# minimega.net
KiCad netlist of a schematic drawn in EAGLE
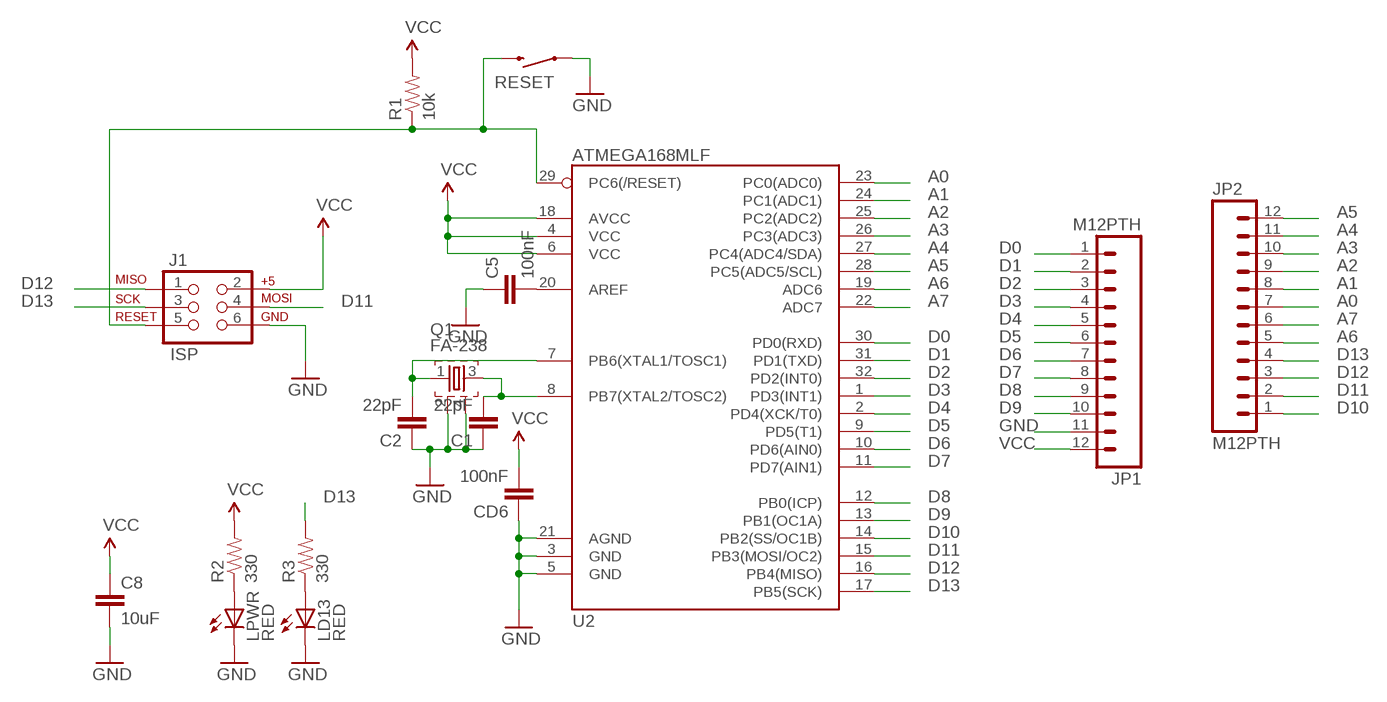
[diagram p0: schematic, sheet 1]

(export (version "E")
  (design (tool "Eeschema 10.0.6"))
  (components
    (comp (ref "C1")
      (value "22pF")
      (footprint "eagle-import:0402-CAP")
      (libsource (lib "eagle-import") (part "10NF-CER"))
    )
    (comp (ref "C2")
      (value "22pF")
      (footprint "eagle-import:0402-CAP")
      (libsource (lib "eagle-import") (part "10NF-CER"))
    )
    (comp (ref "C5")
      (value "100nF")
      (footprint "eagle-import:0402-CAP")
      (libsource (lib "eagle-import") (part "10NF-CER"))
    )
    (comp (ref "C8")
      (value "10uF")
      (footprint "eagle-import:0805")
      (libsource (lib "eagle-import") (part "CAP0805"))
    )
    (comp (ref "CD6")
      (value "100nF")
      (footprint "eagle-import:0402-CAP")
      (libsource (lib "eagle-import") (part "10NF-CER"))
    )
    (comp (ref "J1")
      (value "ISP")
      (footprint "eagle-import:2X3")
      (libsource (lib "eagle-import") (part "AVR_SPI_PRG_6PTH"))
    )
    (comp (ref "JP1")
      (value "M12PTH")
      (footprint "eagle-import:1X12")
      (libsource (lib "eagle-import") (part "M12PTH"))
    )
    (comp (ref "JP2")
      (value "M12PTH")
      (footprint "eagle-import:1X12")
      (libsource (lib "eagle-import") (part "M12PTH"))
    )
    (comp (ref "LD13")
      (value "RED")
      (footprint "eagle-import:LED-0603")
      (libsource (lib "eagle-import") (part "LED-RED0603"))
    )
    (comp (ref "LPWR")
      (value "RED")
      (footprint "eagle-import:LED-0603")
      (libsource (lib "eagle-import") (part "LED-RED0603"))
    )
    (comp (ref "Q1")
      (value "FA-238")
      (footprint "eagle-import:FA-238")
      (libsource (lib "eagle-import") (part "FA-238"))
    )
    (comp (ref "R1")
      (value "10k")
      (footprint "eagle-import:0603-RES")
      (libsource (lib "eagle-import") (part "RESISTOR0603"))
    )
    (comp (ref "R2")
      (value "330")
      (footprint "eagle-import:0603-RES")
      (libsource (lib "eagle-import") (part "RESISTOR0603"))
    )
    (comp (ref "R3")
      (value "330")
      (footprint "eagle-import:0603-RES")
      (libsource (lib "eagle-import") (part "RESISTOR0603"))
    )
    (comp (ref "RESET")
      (value "SWITCH-MOMENTARY-2PTH")
      (footprint "eagle-import:TACTILE-PTH")
      (libsource (lib "eagle-import") (part "SWITCH-MOMENTARY-2PTH"))
    )
    (comp (ref "U2")
      (value "ATMEGA168MLF")
      (footprint "eagle-import:MLF32")
      (libsource (lib "eagle-import") (part "ATMEGA168MLF"))
    )
  )
  (nets
    (net (code "1") (name "/A0") (class "Default")
      (node (ref "JP2") (pin "7") (pinfunction "7_7") (pintype "passive"))
      (node (ref "U2") (pin "23") (pinfunction "PC0(ADC0)_23") (pintype "bidirectional"))
    )
    (net (code "2") (name "/A1") (class "Default")
      (node (ref "JP2") (pin "8") (pinfunction "8_8") (pintype "passive"))
      (node (ref "U2") (pin "24") (pinfunction "PC1(ADC1)_24") (pintype "bidirectional"))
    )
    (net (code "3") (name "/A2") (class "Default")
      (node (ref "JP2") (pin "9") (pinfunction "9_9") (pintype "passive"))
      (node (ref "U2") (pin "25") (pinfunction "PC2(ADC2)_25") (pintype "bidirectional"))
    )
    (net (code "4") (name "/A3") (class "Default")
      (node (ref "JP2") (pin "10") (pinfunction "10_10") (pintype "passive"))
      (node (ref "U2") (pin "26") (pinfunction "PC3(ADC3)_26") (pintype "bidirectional"))
    )
    (net (code "5") (name "/A4") (class "Default")
      (node (ref "JP2") (pin "11") (pinfunction "11_11") (pintype "passive"))
      (node (ref "U2") (pin "27") (pinfunction "PC4(ADC4/SDA)_27") (pintype "bidirectional"))
    )
    (net (code "6") (name "/A5") (class "Default")
      (node (ref "JP2") (pin "12") (pinfunction "12_12") (pintype "passive"))
      (node (ref "U2") (pin "28") (pinfunction "PC5(ADC5/SCL)_28") (pintype "bidirectional"))
    )
    (net (code "7") (name "/A6") (class "Default")
      (node (ref "JP2") (pin "5") (pinfunction "5_5") (pintype "passive"))
      (node (ref "U2") (pin "19") (pinfunction "ADC6_19") (pintype "bidirectional"))
    )
    (net (code "8") (name "/A7") (class "Default")
      (node (ref "JP2") (pin "6") (pinfunction "6_6") (pintype "passive"))
      (node (ref "U2") (pin "22") (pinfunction "ADC7_22") (pintype "bidirectional"))
    )
    (net (code "9") (name "/D0") (class "Default")
      (node (ref "JP1") (pin "1") (pinfunction "1_1") (pintype "passive"))
      (node (ref "U2") (pin "30") (pinfunction "PD0(RXD)_30") (pintype "bidirectional"))
    )
    (net (code "10") (name "/D1") (class "Default")
      (node (ref "JP1") (pin "2") (pinfunction "2_2") (pintype "passive"))
      (node (ref "U2") (pin "31") (pinfunction "PD1(TXD)_31") (pintype "bidirectional"))
    )
    (net (code "11") (name "/D2") (class "Default")
      (node (ref "JP1") (pin "3") (pinfunction "3_3") (pintype "passive"))
      (node (ref "U2") (pin "32") (pinfunction "PD2(INT0)_32") (pintype "bidirectional"))
    )
    (net (code "12") (name "/D3") (class "Default")
      (node (ref "JP1") (pin "4") (pinfunction "4_4") (pintype "passive"))
      (node (ref "U2") (pin "1") (pinfunction "PD3(INT1)_1") (pintype "bidirectional"))
    )
    (net (code "13") (name "/D4") (class "Default")
      (node (ref "JP1") (pin "5") (pinfunction "5_5") (pintype "passive"))
      (node (ref "U2") (pin "2") (pinfunction "PD4(XCK/T0)_2") (pintype "bidirectional"))
    )
    (net (code "14") (name "/D5") (class "Default")
      (node (ref "JP1") (pin "6") (pinfunction "6_6") (pintype "passive"))
      (node (ref "U2") (pin "9") (pinfunction "PD5(T1)_9") (pintype "bidirectional"))
    )
    (net (code "15") (name "/D6") (class "Default")
      (node (ref "JP1") (pin "7") (pinfunction "7_7") (pintype "passive"))
      (node (ref "U2") (pin "10") (pinfunction "PD6(AIN0)_10") (pintype "bidirectional"))
    )
    (net (code "16") (name "/D7") (class "Default")
      (node (ref "JP1") (pin "8") (pinfunction "8_8") (pintype "passive"))
      (node (ref "U2") (pin "11") (pinfunction "PD7(AIN1)_11") (pintype "bidirectional"))
    )
    (net (code "17") (name "/D8") (class "Default")
      (node (ref "JP1") (pin "9") (pinfunction "9_9") (pintype "passive"))
      (node (ref "U2") (pin "12") (pinfunction "PB0(ICP)_12") (pintype "bidirectional"))
    )
    (net (code "18") (name "/D9") (class "Default")
      (node (ref "JP1") (pin "10") (pinfunction "10_10") (pintype "passive"))
      (node (ref "U2") (pin "13") (pinfunction "PB1(OC1A)_13") (pintype "bidirectional"))
    )
    (net (code "19") (name "/D10") (class "Default")
      (node (ref "JP2") (pin "1") (pinfunction "1_1") (pintype "passive"))
      (node (ref "U2") (pin "14") (pinfunction "PB2(SS/OC1B)_14") (pintype "bidirectional"))
    )
    (net (code "20") (name "/D11") (class "Default")
      (node (ref "J1") (pin "4") (pinfunction "4_4") (pintype "passive"))
      (node (ref "JP2") (pin "2") (pinfunction "2_2") (pintype "passive"))
      (node (ref "U2") (pin "15") (pinfunction "PB3(MOSI/OC2)_15") (pintype "bidirectional"))
    )
    (net (code "21") (name "/D12") (class "Default")
      (node (ref "J1") (pin "1") (pinfunction "1_1") (pintype "passive"))
      (node (ref "JP2") (pin "3") (pinfunction "3_3") (pintype "passive"))
      (node (ref "U2") (pin "16") (pinfunction "PB4(MISO)_16") (pintype "bidirectional"))
    )
    (net (code "22") (name "/D13") (class "Default")
      (node (ref "J1") (pin "3") (pinfunction "3_3") (pintype "passive"))
      (node (ref "JP2") (pin "4") (pinfunction "4_4") (pintype "passive"))
      (node (ref "R3") (pin "2") (pinfunction "2_2") (pintype "passive"))
      (node (ref "U2") (pin "17") (pinfunction "PB5(SCK)_17") (pintype "bidirectional"))
    )
    (net (code "23") (name "GND") (class "Default")
      (node (ref "C1") (pin "1") (pinfunction "1_1") (pintype "passive"))
      (node (ref "C2") (pin "1") (pinfunction "1_1") (pintype "passive"))
      (node (ref "C5") (pin "1") (pinfunction "1_1") (pintype "passive"))
      (node (ref "C8") (pin "2") (pinfunction "2_2") (pintype "passive"))
      (node (ref "CD6") (pin "1") (pinfunction "1_1") (pintype "passive"))
      (node (ref "J1") (pin "6") (pinfunction "6_6") (pintype "passive"))
      (node (ref "JP1") (pin "11") (pinfunction "11_11") (pintype "passive"))
      (node (ref "LD13") (pin "C") (pinfunction "C_C") (pintype "passive"))
      (node (ref "LPWR") (pin "C") (pinfunction "C_C") (pintype "passive"))
      (node (ref "Q1") (pin "2") (pinfunction "2_2") (pintype "passive"))
      (node (ref "Q1") (pin "4") (pinfunction "4_4") (pintype "passive"))
      (node (ref "RESET") (pin "1") (pinfunction "1_1") (pintype "passive"))
      (node (ref "U2") (pin "21") (pinfunction "AGND_21") (pintype "bidirectional"))
      (node (ref "U2") (pin "3") (pinfunction "GND_3") (pintype "bidirectional"))
      (node (ref "U2") (pin "5") (pinfunction "GND_5") (pintype "bidirectional"))
    )
    (net (code "24") (name "Net-(LD13-PadA)") (class "Default")
      (node (ref "LD13") (pin "A") (pinfunction "A_A") (pintype "passive"))
      (node (ref "R3") (pin "1") (pinfunction "1_1") (pintype "passive"))
    )
    (net (code "25") (name "Net-(LPWR-PadA)") (class "Default")
      (node (ref "LPWR") (pin "A") (pinfunction "A_A") (pintype "passive"))
      (node (ref "R2") (pin "1") (pinfunction "1_1") (pintype "passive"))
    )
    (net (code "26") (name "Net-(RESET-2)") (class "Default")
      (node (ref "J1") (pin "5") (pinfunction "5_5") (pintype "passive"))
      (node (ref "R1") (pin "1") (pinfunction "1_1") (pintype "passive"))
      (node (ref "RESET") (pin "3") (pinfunction "2_3") (pintype "passive"))
      (node (ref "U2") (pin "29") (pinfunction "PC6(/RESET)_29") (pintype "bidirectional"))
    )
    (net (code "27") (name "Net-(U2-AREF)") (class "Default")
      (node (ref "C5") (pin "2") (pinfunction "2_2") (pintype "passive"))
      (node (ref "U2") (pin "20") (pinfunction "AREF_20") (pintype "bidirectional"))
    )
    (net (code "28") (name "Net-(U2-PB6(XTAL1{slash}TOSC1))") (class "Default")
      (node (ref "C2") (pin "2") (pinfunction "2_2") (pintype "passive"))
      (node (ref "Q1") (pin "1") (pinfunction "1_1") (pintype "passive"))
      (node (ref "U2") (pin "7") (pinfunction "PB6(XTAL1/TOSC1)_7") (pintype "bidirectional"))
    )
    (net (code "29") (name "Net-(U2-PB7(XTAL2{slash}TOSC2))") (class "Default")
      (node (ref "C1") (pin "2") (pinfunction "2_2") (pintype "passive"))
      (node (ref "Q1") (pin "3") (pinfunction "3_3") (pintype "passive"))
      (node (ref "U2") (pin "8") (pinfunction "PB7(XTAL2/TOSC2)_8") (pintype "bidirectional"))
    )
    (net (code "30") (name "VCC") (class "Default")
      (node (ref "C8") (pin "1") (pinfunction "1_1") (pintype "passive"))
      (node (ref "CD6") (pin "2") (pinfunction "2_2") (pintype "passive"))
      (node (ref "J1") (pin "2") (pinfunction "2_2") (pintype "passive"))
      (node (ref "JP1") (pin "12") (pinfunction "12_12") (pintype "passive"))
      (node (ref "R1") (pin "2") (pinfunction "2_2") (pintype "passive"))
      (node (ref "R2") (pin "2") (pinfunction "2_2") (pintype "passive"))
      (node (ref "U2") (pin "18") (pinfunction "AVCC_18") (pintype "bidirectional"))
      (node (ref "U2") (pin "4") (pinfunction "VCC_4") (pintype "bidirectional"))
      (node (ref "U2") (pin "6") (pinfunction "VCC_6") (pintype "bidirectional"))
    )
  )
)
